# NinjaPCB_ver2_0.net
KiCad netlist of a schematic drawn in EAGLE
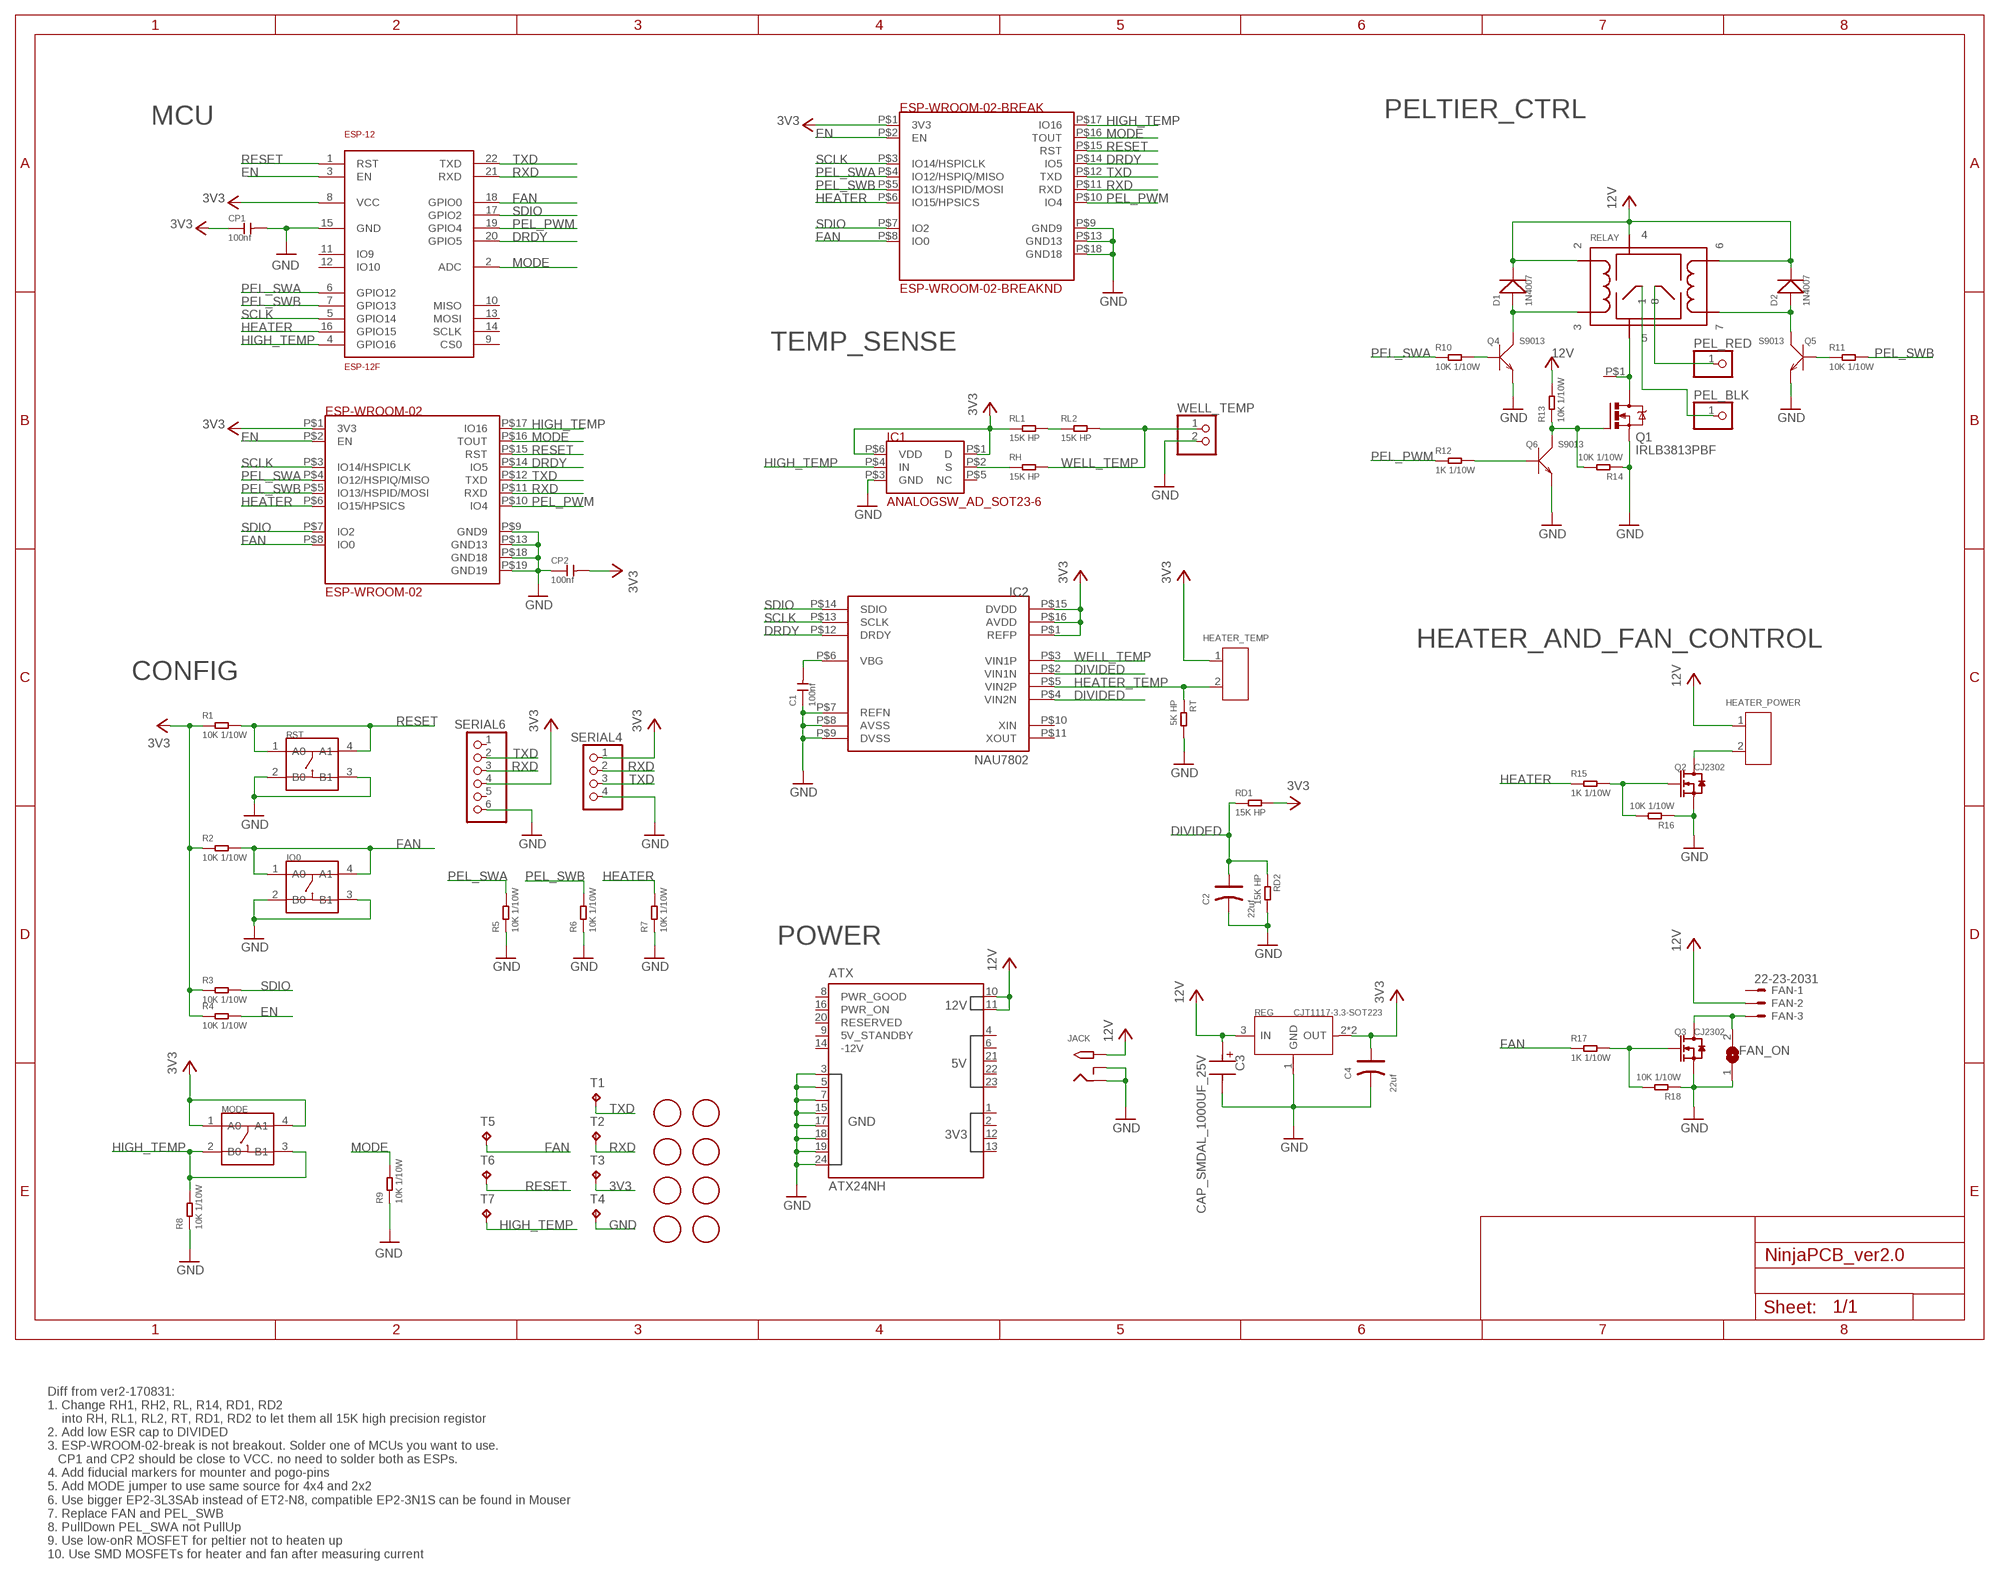
[diagram p0: schematic, sheet 1]

(export (version "E")
  (design (tool "Eeschema 10.0.6"))
  (components
    (comp (ref "ATX")
      (value "ATX24NH")
      (footprint "eagle-import:ATX24")
      (libsource (lib "eagle-import") (part "ATX24NH"))
    )
    (comp (ref "C1")
      (value "100nf")
      (footprint "eagle-import:C0603")
      (fields (field (name "MPN") "CC0603KRX7R9BB104"))
      (libsource (lib "eagle-import") (part "CERAMIC-100NF-50V-10%-X7R(0603)"))
    )
    (comp (ref "C2")
      (value "22uf")
      (footprint "eagle-import:AVX-B")
      (fields (field (name "MPN") "TAJB226*016#NJ"))
      (libsource (lib "eagle-import") (part "TANTALUM-SMD-22UF-16V(AVX-B)"))
    )
    (comp (ref "C3")
      (value "CAP_SMDAL_1000UF_25V")
      (footprint "eagle-import:CAP_SMD_AL_D125")
      (libsource (lib "eagle-import") (part "CAP_SMDAL_1000UF_25V"))
    )
    (comp (ref "C4")
      (value "22uf")
      (footprint "eagle-import:AVX-B")
      (fields (field (name "MPN") "TAJB226*016#NJ"))
      (libsource (lib "eagle-import") (part "TANTALUM-SMD-22UF-16V(AVX-B)"))
    )
    (comp (ref "CP1")
      (value "100nf")
      (footprint "eagle-import:C0603")
      (fields (field (name "MPN") "CC0603KRX7R9BB104"))
      (libsource (lib "eagle-import") (part "CERAMIC-100NF-50V-10%-X7R(0603)"))
    )
    (comp (ref "CP2")
      (value "100nf")
      (footprint "eagle-import:C0603")
      (fields (field (name "MPN") "CC0603KRX7R9BB104"))
      (libsource (lib "eagle-import") (part "CERAMIC-100NF-50V-10%-X7R(0603)"))
    )
    (comp (ref "D1")
      (value "1N4007")
      (footprint "eagle-import:DO-214AC")
      (libsource (lib "eagle-import") (part "DIODE-GEN-PURPOSE-1KV-1A(DO-214AC)"))
    )
    (comp (ref "D2")
      (value "1N4007")
      (footprint "eagle-import:DO-214AC")
      (libsource (lib "eagle-import") (part "DIODE-GEN-PURPOSE-1KV-1A(DO-214AC)"))
    )
    (comp (ref "ESP-12")
      (value "ESP-12F")
      (footprint "eagle-import:ESP-12F")
      (libsource (lib "eagle-import") (part "ESP-12F"))
    )
    (comp (ref "ESP-WROOM-02")
      (value "ESP-WROOM-02")
      (footprint "eagle-import:ESP-WROOM-02")
      (libsource (lib "eagle-import") (part "ESP-WROOM-02"))
    )
    (comp (ref "ESP-WROOM-02-BREAK")
      (value "ESP-WROOM-02-BREAKND")
      (footprint "eagle-import:ESP-WROOM-02-BREAK-NODETAIL")
      (libsource (lib "eagle-import") (part "ESP-WROOM-02-BREAKND"))
    )
    (comp (ref "FAN")
      (value "22-23-2031")
      (footprint "eagle-import:22-23-2031")
      (fields (field (name "MF") "MOLEX"))
      (libsource (lib "eagle-import") (part "22-23-2031"))
    )
    (comp (ref "FAN_ON")
      (value "SJ")
      (footprint "eagle-import:SJ")
      (libsource (lib "eagle-import") (part "SJ"))
    )
    (comp (ref "HEATER_POWER")
      (value "SCREW-TERMINAL-GREEN(2P-3.5)")
      (footprint "eagle-import:H2-3.5-7.0X7.0MM")
      (libsource (lib "eagle-import") (part "SCREW-TERMINAL-GREEN(2P-3.5)"))
    )
    (comp (ref "HEATER_TEMP")
      (value "SCREW-TERMINAL-GREEN(2P-3.5)")
      (footprint "eagle-import:H2-3.5-7.0X7.0MM")
      (libsource (lib "eagle-import") (part "SCREW-TERMINAL-GREEN(2P-3.5)"))
    )
    (comp (ref "HEATSINK")
      (value "HEAT111PB015")
      (footprint "eagle-import:HEAT11PB015")
      (libsource (lib "eagle-import") (part "HEAT111PB015"))
    )
    (comp (ref "IC1")
      (value "ANALOGSW_AD_SOT23-6")
      (footprint "eagle-import:SOT-23-6")
      (libsource (lib "eagle-import") (part "ANALOGSW_AD_SOT23-6"))
    )
    (comp (ref "IC2")
      (value "NAU7802")
      (footprint "eagle-import:SOP-16")
      (libsource (lib "eagle-import") (part "NAU7802"))
    )
    (comp (ref "IO0")
      (value "DIP-SWITCH-TACTILE-SPST-NO/TS-1109(4P-D6.0MM)'TS-1109'")
      (footprint "eagle-import:SW4-6.0X6.0X5.0MM")
      (libsource (lib "eagle-import") (part "DIP-SWITCH-TACTILE-SPST-NO/TS-1109(4P-D6.0MM)'TS-1109'"))
    )
    (comp (ref "JACK")
      (value "2.1MMJACKTHM-NOOUT")
      (footprint "eagle-import:PJ-102A-NOOUT")
      (libsource (lib "eagle-import") (part "2.1MMJACKTHM-NOOUT"))
    )
    (comp (ref "MODE")
      (value "DIP-SWITCH-TACTILE-SPST-NO/TS-1109(4P-D6.0MM)'TS-1109'")
      (footprint "eagle-import:SW4-6.0X6.0X5.0MM")
      (libsource (lib "eagle-import") (part "DIP-SWITCH-TACTILE-SPST-NO/TS-1109(4P-D6.0MM)'TS-1109'"))
    )
    (comp (ref "PEL_BLK")
      (value "PINHD-1X1L")
      (footprint "eagle-import:1X01LONG")
      (libsource (lib "eagle-import") (part "PINHD-1X1L"))
    )
    (comp (ref "PEL_RED")
      (value "PINHD-1X1L")
      (footprint "eagle-import:1X01LONG")
      (libsource (lib "eagle-import") (part "PINHD-1X1L"))
    )
    (comp (ref "Q1")
      (value "IRLB3813PBF")
      (footprint "eagle-import:TO220BV")
      (libsource (lib "eagle-import") (part "IRF520"))
    )
    (comp (ref "Q2")
      (value "CJ2302")
      (footprint "eagle-import:SOT-23")
      (libsource (lib "eagle-import") (part "SMD-MOSFET-N-CH-20V-2.1A-CJ2302(SOT-23)"))
    )
    (comp (ref "Q3")
      (value "CJ2302")
      (footprint "eagle-import:SOT-23")
      (libsource (lib "eagle-import") (part "SMD-MOSFET-N-CH-20V-2.1A-CJ2302(SOT-23)"))
    )
    (comp (ref "Q4")
      (value "S9013")
      (footprint "eagle-import:SOT-23")
      (libsource (lib "eagle-import") (part "SMD-TRANSISTORS-NPN-25V-500MA-S9013(SOT-23)"))
    )
    (comp (ref "Q5")
      (value "S9013")
      (footprint "eagle-import:SOT-23")
      (libsource (lib "eagle-import") (part "SMD-TRANSISTORS-NPN-25V-500MA-S9013(SOT-23)"))
    )
    (comp (ref "Q6")
      (value "S9013")
      (footprint "eagle-import:SOT-23")
      (libsource (lib "eagle-import") (part "SMD-TRANSISTORS-NPN-25V-500MA-S9013(SOT-23)"))
    )
    (comp (ref "R1")
      (value "10K 1/10W")
      (footprint "eagle-import:R0603")
      (fields (field (name "MPN") "RC0603JR-0710KL"))
      (libsource (lib "eagle-import") (part "SMD-RES-10K-5%-1/10W(0603)"))
    )
    (comp (ref "R2")
      (value "10K 1/10W")
      (footprint "eagle-import:R0603")
      (fields (field (name "MPN") "RC0603JR-0710KL"))
      (libsource (lib "eagle-import") (part "SMD-RES-10K-5%-1/10W(0603)"))
    )
    (comp (ref "R3")
      (value "10K 1/10W")
      (footprint "eagle-import:R0603")
      (fields (field (name "MPN") "RC0603JR-0710KL"))
      (libsource (lib "eagle-import") (part "SMD-RES-10K-5%-1/10W(0603)"))
    )
    (comp (ref "R4")
      (value "10K 1/10W")
      (footprint "eagle-import:R0603")
      (fields (field (name "MPN") "RC0603JR-0710KL"))
      (libsource (lib "eagle-import") (part "SMD-RES-10K-5%-1/10W(0603)"))
    )
    (comp (ref "R5")
      (value "10K 1/10W")
      (footprint "eagle-import:R0603")
      (fields (field (name "MPN") "RC0603JR-0710KL"))
      (libsource (lib "eagle-import") (part "SMD-RES-10K-5%-1/10W(0603)"))
    )
    (comp (ref "R6")
      (value "10K 1/10W")
      (footprint "eagle-import:R0603")
      (fields (field (name "MPN") "RC0603JR-0710KL"))
      (libsource (lib "eagle-import") (part "SMD-RES-10K-5%-1/10W(0603)"))
    )
    (comp (ref "R7")
      (value "10K 1/10W")
      (footprint "eagle-import:R0603")
      (fields (field (name "MPN") "RC0603JR-0710KL"))
      (libsource (lib "eagle-import") (part "SMD-RES-10K-5%-1/10W(0603)"))
    )
    (comp (ref "R8")
      (value "10K 1/10W")
      (footprint "eagle-import:R0603")
      (fields (field (name "MPN") "RC0603JR-0710KL"))
      (libsource (lib "eagle-import") (part "SMD-RES-10K-5%-1/10W(0603)"))
    )
    (comp (ref "R9")
      (value "10K 1/10W")
      (footprint "eagle-import:R0603")
      (fields (field (name "MPN") "RC0603JR-0710KL"))
      (libsource (lib "eagle-import") (part "SMD-RES-10K-5%-1/10W(0603)"))
    )
    (comp (ref "R10")
      (value "10K 1/10W")
      (footprint "eagle-import:R0603")
      (fields (field (name "MPN") "RC0603JR-0710KL"))
      (libsource (lib "eagle-import") (part "SMD-RES-10K-5%-1/10W(0603)"))
    )
    (comp (ref "R11")
      (value "10K 1/10W")
      (footprint "eagle-import:R0603")
      (fields (field (name "MPN") "RC0603JR-0710KL"))
      (libsource (lib "eagle-import") (part "SMD-RES-10K-5%-1/10W(0603)"))
    )
    (comp (ref "R12")
      (value "1K 1/10W")
      (footprint "eagle-import:R0603")
      (fields (field (name "MPN") "RC0603JR-071KL"))
      (libsource (lib "eagle-import") (part "SMD-RES-1K-5%-1/10W(0603)"))
    )
    (comp (ref "R13")
      (value "10K 1/10W")
      (footprint "eagle-import:R0603")
      (fields (field (name "MPN") "RC0603JR-0710KL"))
      (libsource (lib "eagle-import") (part "SMD-RES-10K-5%-1/10W(0603)"))
    )
    (comp (ref "R14")
      (value "10K 1/10W")
      (footprint "eagle-import:R0603")
      (fields (field (name "MPN") "RC0603JR-0710KL"))
      (libsource (lib "eagle-import") (part "SMD-RES-10K-5%-1/10W(0603)"))
    )
    (comp (ref "R15")
      (value "1K 1/10W")
      (footprint "eagle-import:R0603")
      (fields (field (name "MPN") "RC0603JR-071KL"))
      (libsource (lib "eagle-import") (part "SMD-RES-1K-5%-1/10W(0603)"))
    )
    (comp (ref "R16")
      (value "10K 1/10W")
      (footprint "eagle-import:R0603")
      (fields (field (name "MPN") "RC0603JR-0710KL"))
      (libsource (lib "eagle-import") (part "SMD-RES-10K-5%-1/10W(0603)"))
    )
    (comp (ref "R17")
      (value "1K 1/10W")
      (footprint "eagle-import:R0603")
      (fields (field (name "MPN") "RC0603JR-071KL"))
      (libsource (lib "eagle-import") (part "SMD-RES-1K-5%-1/10W(0603)"))
    )
    (comp (ref "R18")
      (value "10K 1/10W")
      (footprint "eagle-import:R0603")
      (fields (field (name "MPN") "RC0603JR-0710KL"))
      (libsource (lib "eagle-import") (part "SMD-RES-10K-5%-1/10W(0603)"))
    )
    (comp (ref "RD1")
      (value "15K HP")
      (footprint "eagle-import:R0603")
      (libsource (lib "eagle-import") (part "R0603"))
    )
    (comp (ref "RD2")
      (value "15K HP")
      (footprint "eagle-import:R0603")
      (libsource (lib "eagle-import") (part "R0603"))
    )
    (comp (ref "REG")
      (value "CJT1117-3.3-SOT223")
      (footprint "eagle-import:SOT-223")
      (fields (field (name "MPN") "CJT1117-3.3"))
      (libsource (lib "eagle-import") (part "PMIC-CJT1117-3.3(SOT223)"))
    )
    (comp (ref "RELAY")
      (value "NEC-RELAY2EN2")
      (footprint "eagle-import:NEC-EN2")
      (libsource (lib "eagle-import") (part "NEC-RELAY2EN2"))
    )
    (comp (ref "RH")
      (value "15K HP")
      (footprint "eagle-import:R0603")
      (libsource (lib "eagle-import") (part "R0603"))
    )
    (comp (ref "RL1")
      (value "15K HP")
      (footprint "eagle-import:R0603")
      (libsource (lib "eagle-import") (part "R0603"))
    )
    (comp (ref "RL2")
      (value "15K HP")
      (footprint "eagle-import:R0603")
      (libsource (lib "eagle-import") (part "R0603"))
    )
    (comp (ref "RST")
      (value "DIP-SWITCH-TACTILE-SPST-NO/TS-1109(4P-D6.0MM)'TS-1109'")
      (footprint "eagle-import:SW4-6.0X6.0X5.0MM")
      (libsource (lib "eagle-import") (part "DIP-SWITCH-TACTILE-SPST-NO/TS-1109(4P-D6.0MM)'TS-1109'"))
    )
    (comp (ref "RT")
      (value "5K HP")
      (footprint "eagle-import:R0603")
      (fields (field (name "MPN") "RC0603FR-072KL"))
      (libsource (lib "eagle-import") (part "SMD-RES-2K-1%-1/10W(0603)"))
    )
    (comp (ref "SERIAL4")
      (value "PINHD-1X4")
      (footprint "eagle-import:1X04")
      (libsource (lib "eagle-import") (part "PINHD-1X4"))
    )
    (comp (ref "SERIAL6")
      (value "PINHD-1X6")
      (footprint "eagle-import:1X06")
      (libsource (lib "eagle-import") (part "PINHD-1X6"))
    )
    (comp (ref "T1")
      (value "TPTP20R")
      (footprint "eagle-import:TP20R")
      (libsource (lib "eagle-import") (part "TPTP20R"))
    )
    (comp (ref "T2")
      (value "TPTP20R")
      (footprint "eagle-import:TP20R")
      (libsource (lib "eagle-import") (part "TPTP20R"))
    )
    (comp (ref "T3")
      (value "TPTP20R")
      (footprint "eagle-import:TP20R")
      (libsource (lib "eagle-import") (part "TPTP20R"))
    )
    (comp (ref "T4")
      (value "TPTP20R")
      (footprint "eagle-import:TP20R")
      (libsource (lib "eagle-import") (part "TPTP20R"))
    )
    (comp (ref "T5")
      (value "TPTP20R")
      (footprint "eagle-import:TP20R")
      (libsource (lib "eagle-import") (part "TPTP20R"))
    )
    (comp (ref "T6")
      (value "TPTP20R")
      (footprint "eagle-import:TP20R")
      (libsource (lib "eagle-import") (part "TPTP20R"))
    )
    (comp (ref "T7")
      (value "TPTP20R")
      (footprint "eagle-import:TP20R")
      (libsource (lib "eagle-import") (part "TPTP20R"))
    )
    (comp (ref "U$3")
      (value "FIDUCIAL")
      (footprint "eagle-import:FIDUCIAL_1MM")
      (libsource (lib "eagle-import") (part "FIDUCIAL"))
    )
    (comp (ref "U$4")
      (value "FIDUCIAL")
      (footprint "eagle-import:FIDUCIAL_1MM")
      (libsource (lib "eagle-import") (part "FIDUCIAL"))
    )
    (comp (ref "U$5")
      (value "FIDUCIAL")
      (footprint "eagle-import:FIDUCIAL_1MM")
      (libsource (lib "eagle-import") (part "FIDUCIAL"))
    )
    (comp (ref "U$6")
      (value "FIDUCIAL")
      (footprint "eagle-import:FIDUCIAL_1MM")
      (libsource (lib "eagle-import") (part "FIDUCIAL"))
    )
    (comp (ref "U$7")
      (value "FIDUCIAL")
      (footprint "eagle-import:FIDUCIAL_1MM")
      (libsource (lib "eagle-import") (part "FIDUCIAL"))
    )
    (comp (ref "U$8")
      (value "FIDUCIAL")
      (footprint "eagle-import:FIDUCIAL_1MM")
      (libsource (lib "eagle-import") (part "FIDUCIAL"))
    )
    (comp (ref "U$9")
      (value "FIDUCIAL")
      (footprint "eagle-import:FIDUCIAL_1MM")
      (libsource (lib "eagle-import") (part "FIDUCIAL"))
    )
    (comp (ref "U$10")
      (value "FIDUCIAL")
      (footprint "eagle-import:FIDUCIAL_1MM")
      (libsource (lib "eagle-import") (part "FIDUCIAL"))
    )
    (comp (ref "WELL_TEMP")
      (value "PINHD-1X2")
      (footprint "eagle-import:1X02")
      (libsource (lib "eagle-import") (part "PINHD-1X2"))
    )
  )
  (nets
    (net (code "1") (name "/DIVIDED") (class "Default")
      (node (ref "C2") (pin "+") (pinfunction "+_+") (pintype "passive"))
      (node (ref "IC2") (pin "P$2") (pinfunction "VIN1N_P$2") (pintype "bidirectional"))
      (node (ref "IC2") (pin "P$4") (pinfunction "VIN2N_P$4") (pintype "bidirectional"))
      (node (ref "RD1") (pin "1") (pinfunction "1_1") (pintype "passive"))
      (node (ref "RD2") (pin "1") (pinfunction "1_1") (pintype "passive"))
    )
    (net (code "2") (name "/DRDY") (class "Default")
      (node (ref "ESP-12") (pin "20") (pinfunction "GPIO5_20") (pintype "bidirectional"))
      (node (ref "ESP-WROOM-02") (pin "P$14") (pinfunction "IO5_P$14") (pintype "bidirectional"))
      (node (ref "ESP-WROOM-02-BREAK") (pin "P$14") (pinfunction "IO5_P$14") (pintype "bidirectional"))
      (node (ref "IC2") (pin "P$12") (pinfunction "DRDY_P$12") (pintype "bidirectional"))
    )
    (net (code "3") (name "/EN") (class "Default")
      (node (ref "ESP-12") (pin "3") (pinfunction "EN_3") (pintype "bidirectional"))
      (node (ref "ESP-WROOM-02") (pin "P$2") (pinfunction "EN_P$2") (pintype "bidirectional"))
      (node (ref "ESP-WROOM-02-BREAK") (pin "P$2") (pinfunction "EN_P$2") (pintype "bidirectional"))
      (node (ref "R4") (pin "2") (pinfunction "2_2") (pintype "passive"))
    )
    (net (code "4") (name "/FAN") (class "Default")
      (node (ref "ESP-12") (pin "18") (pinfunction "GPIO0_18") (pintype "bidirectional"))
      (node (ref "ESP-WROOM-02") (pin "P$8") (pinfunction "IO0_P$8") (pintype "bidirectional"))
      (node (ref "ESP-WROOM-02-BREAK") (pin "P$8") (pinfunction "IO0_P$8") (pintype "bidirectional"))
      (node (ref "IO0") (pin "1") (pinfunction "A0_1") (pintype "bidirectional"))
      (node (ref "IO0") (pin "4") (pinfunction "A1_4") (pintype "bidirectional"))
      (node (ref "R17") (pin "1") (pinfunction "1_1") (pintype "passive"))
      (node (ref "R2") (pin "2") (pinfunction "2_2") (pintype "passive"))
      (node (ref "T5") (pin "TP") (pinfunction "TP_TP") (pintype "input"))
    )
    (net (code "5") (name "/HEATER") (class "Default")
      (node (ref "ESP-12") (pin "16") (pinfunction "GPIO15_16") (pintype "bidirectional"))
      (node (ref "ESP-WROOM-02") (pin "P$6") (pinfunction "IO15/HPSICS_P$6") (pintype "bidirectional"))
      (node (ref "ESP-WROOM-02-BREAK") (pin "P$6") (pinfunction "IO15/HPSICS_P$6") (pintype "bidirectional"))
      (node (ref "R15") (pin "1") (pinfunction "1_1") (pintype "passive"))
      (node (ref "R7") (pin "2") (pinfunction "2_2") (pintype "passive"))
    )
    (net (code "6") (name "/HEATER_TEMP") (class "Default")
      (node (ref "HEATER_TEMP") (pin "2") (pinfunction "2_2") (pintype "bidirectional"))
      (node (ref "IC2") (pin "P$5") (pinfunction "VIN2P_P$5") (pintype "bidirectional"))
      (node (ref "RT") (pin "1") (pinfunction "1_1") (pintype "passive"))
    )
    (net (code "7") (name "/HIGH_TEMP") (class "Default")
      (node (ref "ESP-12") (pin "4") (pinfunction "GPIO16_4") (pintype "bidirectional"))
      (node (ref "ESP-WROOM-02") (pin "P$17") (pinfunction "IO16_P$17") (pintype "bidirectional"))
      (node (ref "ESP-WROOM-02-BREAK") (pin "P$17") (pinfunction "IO16_P$17") (pintype "bidirectional"))
      (node (ref "IC1") (pin "P$4") (pinfunction "IN_P$4") (pintype "bidirectional"))
      (node (ref "MODE") (pin "2") (pinfunction "B0_2") (pintype "bidirectional"))
      (node (ref "MODE") (pin "3") (pinfunction "B1_3") (pintype "bidirectional"))
      (node (ref "R8") (pin "2") (pinfunction "2_2") (pintype "passive"))
      (node (ref "T7") (pin "TP") (pinfunction "TP_TP") (pintype "input"))
    )
    (net (code "8") (name "/MODE") (class "Default")
      (node (ref "ESP-12") (pin "2") (pinfunction "ADC_2") (pintype "bidirectional"))
      (node (ref "ESP-WROOM-02") (pin "P$16") (pinfunction "TOUT_P$16") (pintype "bidirectional"))
      (node (ref "ESP-WROOM-02-BREAK") (pin "P$16") (pinfunction "TOUT_P$16") (pintype "bidirectional"))
      (node (ref "R9") (pin "2") (pinfunction "2_2") (pintype "passive"))
    )
    (net (code "9") (name "/PEL_PWM") (class "Default")
      (node (ref "ESP-12") (pin "19") (pinfunction "GPIO4_19") (pintype "bidirectional"))
      (node (ref "ESP-WROOM-02") (pin "P$10") (pinfunction "IO4_P$10") (pintype "bidirectional"))
      (node (ref "ESP-WROOM-02-BREAK") (pin "P$10") (pinfunction "IO4_P$10") (pintype "bidirectional"))
      (node (ref "R12") (pin "1") (pinfunction "1_1") (pintype "passive"))
    )
    (net (code "10") (name "/PEL_SWA") (class "Default")
      (node (ref "ESP-12") (pin "6") (pinfunction "GPIO12_6") (pintype "bidirectional"))
      (node (ref "ESP-WROOM-02") (pin "P$4") (pinfunction "IO12/HSPIQ/MISO_P$4") (pintype "bidirectional"))
      (node (ref "ESP-WROOM-02-BREAK") (pin "P$4") (pinfunction "IO12/HSPIQ/MISO_P$4") (pintype "bidirectional"))
      (node (ref "R10") (pin "1") (pinfunction "1_1") (pintype "passive"))
      (node (ref "R5") (pin "2") (pinfunction "2_2") (pintype "passive"))
    )
    (net (code "11") (name "/PEL_SWB") (class "Default")
      (node (ref "ESP-12") (pin "7") (pinfunction "GPIO13_7") (pintype "bidirectional"))
      (node (ref "ESP-WROOM-02") (pin "P$5") (pinfunction "IO13/HSPID/MOSI_P$5") (pintype "bidirectional"))
      (node (ref "ESP-WROOM-02-BREAK") (pin "P$5") (pinfunction "IO13/HSPID/MOSI_P$5") (pintype "bidirectional"))
      (node (ref "R11") (pin "2") (pinfunction "2_2") (pintype "passive"))
      (node (ref "R6") (pin "2") (pinfunction "2_2") (pintype "passive"))
    )
    (net (code "12") (name "/RESET") (class "Default")
      (node (ref "ESP-12") (pin "1") (pinfunction "RST_1") (pintype "bidirectional"))
      (node (ref "ESP-WROOM-02") (pin "P$15") (pinfunction "RST_P$15") (pintype "bidirectional"))
      (node (ref "ESP-WROOM-02-BREAK") (pin "P$15") (pinfunction "RST_P$15") (pintype "bidirectional"))
      (node (ref "R1") (pin "2") (pinfunction "2_2") (pintype "passive"))
      (node (ref "RST") (pin "1") (pinfunction "A0_1") (pintype "bidirectional"))
      (node (ref "RST") (pin "4") (pinfunction "A1_4") (pintype "bidirectional"))
      (node (ref "T6") (pin "TP") (pinfunction "TP_TP") (pintype "input"))
    )
    (net (code "13") (name "/RXD") (class "Default")
      (node (ref "ESP-12") (pin "21") (pinfunction "RXD_21") (pintype "bidirectional"))
      (node (ref "ESP-WROOM-02") (pin "P$11") (pinfunction "RXD_P$11") (pintype "bidirectional"))
      (node (ref "ESP-WROOM-02-BREAK") (pin "P$11") (pinfunction "RXD_P$11") (pintype "bidirectional"))
      (node (ref "SERIAL4") (pin "2") (pinfunction "2_2") (pintype "passive"))
      (node (ref "SERIAL6") (pin "3") (pinfunction "3_3") (pintype "passive"))
      (node (ref "T2") (pin "TP") (pinfunction "TP_TP") (pintype "input"))
    )
    (net (code "14") (name "/SCLK") (class "Default")
      (node (ref "ESP-12") (pin "5") (pinfunction "GPIO14_5") (pintype "bidirectional"))
      (node (ref "ESP-WROOM-02") (pin "P$3") (pinfunction "IO14/HSPICLK_P$3") (pintype "bidirectional"))
      (node (ref "ESP-WROOM-02-BREAK") (pin "P$3") (pinfunction "IO14/HSPICLK_P$3") (pintype "bidirectional"))
      (node (ref "IC2") (pin "P$13") (pinfunction "SCLK_P$13") (pintype "bidirectional"))
    )
    (net (code "15") (name "/SDIO") (class "Default")
      (node (ref "ESP-12") (pin "17") (pinfunction "GPIO2_17") (pintype "bidirectional"))
      (node (ref "ESP-WROOM-02") (pin "P$7") (pinfunction "IO2_P$7") (pintype "bidirectional"))
      (node (ref "ESP-WROOM-02-BREAK") (pin "P$7") (pinfunction "IO2_P$7") (pintype "bidirectional"))
      (node (ref "IC2") (pin "P$14") (pinfunction "SDIO_P$14") (pintype "bidirectional"))
      (node (ref "R3") (pin "2") (pinfunction "2_2") (pintype "passive"))
    )
    (net (code "16") (name "/TXD") (class "Default")
      (node (ref "ESP-12") (pin "22") (pinfunction "TXD_22") (pintype "bidirectional"))
      (node (ref "ESP-WROOM-02") (pin "P$12") (pinfunction "TXD_P$12") (pintype "bidirectional"))
      (node (ref "ESP-WROOM-02-BREAK") (pin "P$12") (pinfunction "TXD_P$12") (pintype "bidirectional"))
      (node (ref "SERIAL4") (pin "3") (pinfunction "3_3") (pintype "passive"))
      (node (ref "SERIAL6") (pin "2") (pinfunction "2_2") (pintype "passive"))
      (node (ref "T1") (pin "TP") (pinfunction "TP_TP") (pintype "input"))
    )
    (net (code "17") (name "/WELL_TEMP") (class "Default")
      (node (ref "IC2") (pin "P$3") (pinfunction "VIN1P_P$3") (pintype "bidirectional"))
      (node (ref "RH") (pin "2") (pinfunction "2_2") (pintype "passive"))
      (node (ref "RL2") (pin "2") (pinfunction "2_2") (pintype "passive"))
      (node (ref "WELL_TEMP") (pin "1") (pinfunction "1_1") (pintype "passive"))
    )
    (net (code "18") (name "3V3") (class "Default")
      (node (ref "C4") (pin "+") (pinfunction "+_+") (pintype "passive"))
      (node (ref "CP1") (pin "1") (pinfunction "1_1") (pintype "passive"))
      (node (ref "CP2") (pin "2") (pinfunction "2_2") (pintype "passive"))
      (node (ref "ESP-12") (pin "8") (pinfunction "VCC_8") (pintype "bidirectional"))
      (node (ref "ESP-WROOM-02") (pin "P$1") (pinfunction "3V3_P$1") (pintype "bidirectional"))
      (node (ref "ESP-WROOM-02-BREAK") (pin "P$1") (pinfunction "3V3_P$1") (pintype "bidirectional"))
      (node (ref "HEATER_TEMP") (pin "1") (pinfunction "1_1") (pintype "bidirectional"))
      (node (ref "IC1") (pin "P$1") (pinfunction "D_P$1") (pintype "bidirectional"))
      (node (ref "IC1") (pin "P$6") (pinfunction "VDD_P$6") (pintype "bidirectional"))
      (node (ref "IC2") (pin "P$1") (pinfunction "REFP_P$1") (pintype "bidirectional"))
      (node (ref "IC2") (pin "P$15") (pinfunction "DVDD_P$15") (pintype "bidirectional"))
      (node (ref "IC2") (pin "P$16") (pinfunction "AVDD_P$16") (pintype "bidirectional"))
      (node (ref "MODE") (pin "1") (pinfunction "A0_1") (pintype "bidirectional"))
      (node (ref "MODE") (pin "4") (pinfunction "A1_4") (pintype "bidirectional"))
      (node (ref "R1") (pin "1") (pinfunction "1_1") (pintype "passive"))
      (node (ref "R2") (pin "1") (pinfunction "1_1") (pintype "passive"))
      (node (ref "R3") (pin "1") (pinfunction "1_1") (pintype "passive"))
      (node (ref "R4") (pin "1") (pinfunction "1_1") (pintype "passive"))
      (node (ref "RD1") (pin "2") (pinfunction "2_2") (pintype "passive"))
      (node (ref "REG") (pin "2") (pinfunction "OUT_2") (pintype "bidirectional"))
      (node (ref "REG") (pin "TER") (pinfunction "OUT_TER") (pintype "bidirectional"))
      (node (ref "RL1") (pin "1") (pinfunction "1_1") (pintype "passive"))
      (node (ref "SERIAL4") (pin "1") (pinfunction "1_1") (pintype "passive"))
      (node (ref "SERIAL6") (pin "4") (pinfunction "4_4") (pintype "passive"))
      (node (ref "T3") (pin "TP") (pinfunction "TP_TP") (pintype "input"))
    )
    (net (code "19") (name "12V") (class "Default")
      (node (ref "ATX") (pin "10") (pinfunction "12V_10_10") (pintype "bidirectional"))
      (node (ref "ATX") (pin "11") (pinfunction "12V_11_11") (pintype "bidirectional"))
      (node (ref "C3") (pin "P$P") (pinfunction "P$P_P$P") (pintype "passive"))
      (node (ref "D1") (pin "2") (pinfunction "-_2") (pintype "passive"))
      (node (ref "D2") (pin "2") (pinfunction "-_2") (pintype "passive"))
      (node (ref "FAN") (pin "2") (pinfunction "S_2") (pintype "passive"))
      (node (ref "HEATER_POWER") (pin "1") (pinfunction "1_1") (pintype "bidirectional"))
      (node (ref "JACK") (pin "TIP") (pinfunction "TIP_TIP") (pintype "bidirectional"))
      (node (ref "R13") (pin "2") (pinfunction "2_2") (pintype "passive"))
      (node (ref "REG") (pin "3") (pinfunction "IN_3") (pintype "bidirectional"))
      (node (ref "RELAY") (pin "P$2") (pinfunction "2_P$2") (pintype "bidirectional"))
      (node (ref "RELAY") (pin "P$4") (pinfunction "4_P$4") (pintype "bidirectional"))
      (node (ref "RELAY") (pin "P$6") (pinfunction "6_P$6") (pintype "bidirectional"))
    )
    (net (code "20") (name "GND") (class "Default")
      (node (ref "ATX") (pin "15") (pinfunction "GND15_15") (pintype "bidirectional"))
      (node (ref "ATX") (pin "17") (pinfunction "GND17_17") (pintype "bidirectional"))
      (node (ref "ATX") (pin "18") (pinfunction "GND18_18") (pintype "bidirectional"))
      (node (ref "ATX") (pin "19") (pinfunction "GND19_19") (pintype "bidirectional"))
      (node (ref "ATX") (pin "24") (pinfunction "GND24_24") (pintype "bidirectional"))
      (node (ref "ATX") (pin "3") (pinfunction "GND3_3") (pintype "bidirectional"))
      (node (ref "ATX") (pin "5") (pinfunction "GND5_5") (pintype "bidirectional"))
      (node (ref "ATX") (pin "7") (pinfunction "GND7_7") (pintype "bidirectional"))
      (node (ref "C1") (pin "1") (pinfunction "1_1") (pintype "passive"))
      (node (ref "C2") (pin "-") (pinfunction "-_-") (pintype "passive"))
      (node (ref "C3") (pin "P$M") (pinfunction "P$M_P$M") (pintype "passive"))
      (node (ref "C4") (pin "-") (pinfunction "-_-") (pintype "passive"))
      (node (ref "CP1") (pin "2") (pinfunction "2_2") (pintype "passive"))
      (node (ref "CP2") (pin "1") (pinfunction "1_1") (pintype "passive"))
      (node (ref "ESP-12") (pin "15") (pinfunction "GND_15") (pintype "bidirectional"))
      (node (ref "ESP-WROOM-02") (pin "P$13") (pinfunction "GND13_P$13") (pintype "bidirectional"))
      (node (ref "ESP-WROOM-02") (pin "P$18") (pinfunction "GND18_P$18") (pintype "bidirectional"))
      (node (ref "ESP-WROOM-02") (pin "P$19") (pinfunction "GND19_P$19") (pintype "bidirectional"))
      (node (ref "ESP-WROOM-02") (pin "P$9") (pinfunction "GND9_P$9") (pintype "bidirectional"))
      (node (ref "ESP-WROOM-02-BREAK") (pin "P$13") (pinfunction "GND13_P$13") (pintype "bidirectional"))
      (node (ref "ESP-WROOM-02-BREAK") (pin "P$18") (pinfunction "GND18_P$18") (pintype "bidirectional"))
      (node (ref "ESP-WROOM-02-BREAK") (pin "P$9") (pinfunction "GND9_P$9") (pintype "bidirectional"))
      (node (ref "FAN_ON") (pin "1") (pinfunction "1_1") (pintype "passive"))
      (node (ref "IC1") (pin "P$3") (pinfunction "GND_P$3") (pintype "bidirectional"))
      (node (ref "IC2") (pin "P$7") (pinfunction "REFN_P$7") (pintype "bidirectional"))
      (node (ref "IC2") (pin "P$8") (pinfunction "AVSS_P$8") (pintype "bidirectional"))
      (node (ref "IC2") (pin "P$9") (pinfunction "DVSS_P$9") (pintype "bidirectional"))
      (node (ref "IO0") (pin "2") (pinfunction "B0_2") (pintype "bidirectional"))
      (node (ref "IO0") (pin "3") (pinfunction "B1_3") (pintype "bidirectional"))
      (node (ref "JACK") (pin "RING") (pinfunction "RING_RING") (pintype "bidirectional"))
      (node (ref "JACK") (pin "RING_SW") (pinfunction "RING_SW_RING_SW") (pintype "bidirectional"))
      (node (ref "Q1") (pin "S") (pinfunction "S_S") (pintype "passive"))
      (node (ref "Q2") (pin "2") (pinfunction "S_2") (pintype "passive"))
      (node (ref "Q3") (pin "2") (pinfunction "S_2") (pintype "passive"))
      (node (ref "Q4") (pin "2") (pinfunction "E_2") (pintype "passive"))
      (node (ref "Q5") (pin "2") (pinfunction "E_2") (pintype "passive"))
      (node (ref "Q6") (pin "2") (pinfunction "E_2") (pintype "passive"))
      (node (ref "R14") (pin "1") (pinfunction "1_1") (pintype "passive"))
      (node (ref "R16") (pin "1") (pinfunction "1_1") (pintype "passive"))
      (node (ref "R18") (pin "1") (pinfunction "1_1") (pintype "passive"))
      (node (ref "R5") (pin "1") (pinfunction "1_1") (pintype "passive"))
      (node (ref "R6") (pin "1") (pinfunction "1_1") (pintype "passive"))
      (node (ref "R7") (pin "1") (pinfunction "1_1") (pintype "passive"))
      (node (ref "R8") (pin "1") (pinfunction "1_1") (pintype "passive"))
      (node (ref "R9") (pin "1") (pinfunction "1_1") (pintype "passive"))
      (node (ref "RD2") (pin "2") (pinfunction "2_2") (pintype "passive"))
      (node (ref "REG") (pin "1") (pinfunction "GND_1") (pintype "bidirectional"))
      (node (ref "RST") (pin "2") (pinfunction "B0_2") (pintype "bidirectional"))
      (node (ref "RST") (pin "3") (pinfunction "B1_3") (pintype "bidirectional"))
      (node (ref "RT") (pin "2") (pinfunction "2_2") (pintype "passive"))
      (node (ref "SERIAL4") (pin "4") (pinfunction "4_4") (pintype "passive"))
      (node (ref "SERIAL6") (pin "6") (pinfunction "6_6") (pintype "passive"))
      (node (ref "T4") (pin "TP") (pinfunction "TP_TP") (pintype "input"))
      (node (ref "WELL_TEMP") (pin "2") (pinfunction "2_2") (pintype "passive"))
    )
    (net (code "21") (name "Net-(D1-+)") (class "Default")
      (node (ref "D1") (pin "1") (pinfunction "+_1") (pintype "passive"))
      (node (ref "Q4") (pin "3") (pinfunction "C_3") (pintype "passive"))
      (node (ref "RELAY") (pin "P$3") (pinfunction "3_P$3") (pintype "bidirectional"))
    )
    (net (code "22") (name "Net-(D2-+)") (class "Default")
      (node (ref "D2") (pin "1") (pinfunction "+_1") (pintype "passive"))
      (node (ref "Q5") (pin "3") (pinfunction "C_3") (pintype "passive"))
      (node (ref "RELAY") (pin "P$7") (pinfunction "7_P$7") (pintype "bidirectional"))
    )
    (net (code "23") (name "Net-(FANC-S)") (class "Default")
      (node (ref "FAN") (pin "3") (pinfunction "S_3") (pintype "passive"))
      (node (ref "FAN_ON") (pin "2") (pinfunction "2_2") (pintype "passive"))
      (node (ref "Q3") (pin "3") (pinfunction "D_3") (pintype "passive"))
    )
    (net (code "24") (name "Net-(IC1-S)") (class "Default")
      (node (ref "IC1") (pin "P$2") (pinfunction "S_P$2") (pintype "bidirectional"))
      (node (ref "RH") (pin "1") (pinfunction "1_1") (pintype "passive"))
    )
    (net (code "25") (name "Net-(IC2-VBG)") (class "Default")
      (node (ref "C1") (pin "2") (pinfunction "2_2") (pintype "passive"))
      (node (ref "IC2") (pin "P$6") (pinfunction "VBG_P$6") (pintype "bidirectional"))
    )
    (net (code "26") (name "Net-(Q2-D)") (class "Default")
      (node (ref "HEATER_POWER") (pin "2") (pinfunction "2_2") (pintype "bidirectional"))
      (node (ref "Q2") (pin "3") (pinfunction "D_3") (pintype "passive"))
    )
    (net (code "27") (name "Net-(Q2-G)") (class "Default")
      (node (ref "Q2") (pin "1") (pinfunction "G_1") (pintype "passive"))
      (node (ref "R15") (pin "2") (pinfunction "2_2") (pintype "passive"))
      (node (ref "R16") (pin "2") (pinfunction "2_2") (pintype "passive"))
    )
    (net (code "28") (name "Net-(Q3-G)") (class "Default")
      (node (ref "Q3") (pin "1") (pinfunction "G_1") (pintype "passive"))
      (node (ref "R17") (pin "2") (pinfunction "2_2") (pintype "passive"))
      (node (ref "R18") (pin "2") (pinfunction "2_2") (pintype "passive"))
    )
    (net (code "29") (name "Net-(Q4-B)") (class "Default")
      (node (ref "Q4") (pin "1") (pinfunction "B_1") (pintype "passive"))
      (node (ref "R10") (pin "2") (pinfunction "2_2") (pintype "passive"))
    )
    (net (code "30") (name "Net-(Q5-B)") (class "Default")
      (node (ref "Q5") (pin "1") (pinfunction "B_1") (pintype "passive"))
      (node (ref "R11") (pin "1") (pinfunction "1_1") (pintype "passive"))
    )
    (net (code "31") (name "Net-(Q6-B)") (class "Default")
      (node (ref "Q6") (pin "1") (pinfunction "B_1") (pintype "passive"))
      (node (ref "R12") (pin "2") (pinfunction "2_2") (pintype "passive"))
    )
    (net (code "32") (name "Net-(Q6-C)") (class "Default")
      (node (ref "Q1") (pin "G") (pinfunction "G_G") (pintype "passive"))
      (node (ref "Q6") (pin "3") (pinfunction "C_3") (pintype "passive"))
      (node (ref "R13") (pin "1") (pinfunction "1_1") (pintype "passive"))
      (node (ref "R14") (pin "2") (pinfunction "2_2") (pintype "passive"))
    )
    (net (code "33") (name "Net-(RELAY-1)") (class "Default")
      (node (ref "PEL_BLK") (pin "1") (pinfunction "1_1") (pintype "passive"))
      (node (ref "RELAY") (pin "P$1") (pinfunction "1_P$1") (pintype "bidirectional"))
    )
    (net (code "34") (name "Net-(RELAY-5)") (class "Default")
      (node (ref "HEATSINK") (pin "P$1") (pinfunction "P$1_P$1") (pintype "bidirectional"))
      (node (ref "Q1") (pin "D") (pinfunction "D_D") (pintype "passive"))
      (node (ref "RELAY") (pin "P$5") (pinfunction "5_P$5") (pintype "bidirectional"))
    )
    (net (code "35") (name "Net-(RELAY-8)") (class "Default")
      (node (ref "PEL_RED") (pin "1") (pinfunction "1_1") (pintype "passive"))
      (node (ref "RELAY") (pin "P$8") (pinfunction "8_P$8") (pintype "bidirectional"))
    )
    (net (code "36") (name "Net-(RL1-Pad2)") (class "Default")
      (node (ref "RL1") (pin "2") (pinfunction "2_2") (pintype "passive"))
      (node (ref "RL2") (pin "1") (pinfunction "1_1") (pintype "passive"))
    )
    (net (code "37") (name "unconnected-(ATX--12V-Pad14)") (class "Default")
      (node (ref "ATX") (pin "14") (pinfunction "-12V_14") (pintype "bidirectional"))
    )
    (net (code "38") (name "unconnected-(ATX-3V3_1-Pad1)") (class "Default")
      (node (ref "ATX") (pin "1") (pinfunction "3V3_1_1") (pintype "bidirectional"))
    )
    (net (code "39") (name "unconnected-(ATX-3V3_2-Pad2)") (class "Default")
      (node (ref "ATX") (pin "2") (pinfunction "3V3_2_2") (pintype "bidirectional"))
    )
    (net (code "40") (name "unconnected-(ATX-3V3_12-Pad12)") (class "Default")
      (node (ref "ATX") (pin "12") (pinfunction "3V3_12_12") (pintype "bidirectional"))
    )
    (net (code "41") (name "unconnected-(ATX-3V3_13-Pad13)") (class "Default")
      (node (ref "ATX") (pin "13") (pinfunction "3V3_13_13") (pintype "bidirectional"))
    )
    (net (code "42") (name "unconnected-(ATX-5V_4-Pad4)") (class "Default")
      (node (ref "ATX") (pin "4") (pinfunction "5V_4_4") (pintype "bidirectional"))
    )
    (net (code "43") (name "unconnected-(ATX-5V_6-Pad6)") (class "Default")
      (node (ref "ATX") (pin "6") (pinfunction "5V_6_6") (pintype "bidirectional"))
    )
    (net (code "44") (name "unconnected-(ATX-5V_21-Pad21)") (class "Default")
      (node (ref "ATX") (pin "21") (pinfunction "5V_21_21") (pintype "bidirectional"))
    )
    (net (code "45") (name "unconnected-(ATX-5V_22-Pad22)") (class "Default")
      (node (ref "ATX") (pin "22") (pinfunction "5V_22_22") (pintype "bidirectional"))
    )
    (net (code "46") (name "unconnected-(ATX-5V_23-Pad23)") (class "Default")
      (node (ref "ATX") (pin "23") (pinfunction "5V_23_23") (pintype "bidirectional"))
    )
    (net (code "47") (name "unconnected-(ATX-5V_STANDBY-Pad9)") (class "Default")
      (node (ref "ATX") (pin "9") (pinfunction "5V_STANDBY_9") (pintype "bidirectional"))
    )
    (net (code "48") (name "unconnected-(ATX-PWR_GOOD-Pad8)") (class "Default")
      (node (ref "ATX") (pin "8") (pinfunction "PWR_GOOD_8") (pintype "bidirectional"))
    )
    (net (code "49") (name "unconnected-(ATX-PWR_ON-Pad16)") (class "Default")
      (node (ref "ATX") (pin "16") (pinfunction "PWR_ON_16") (pintype "bidirectional"))
    )
    (net (code "50") (name "unconnected-(ATX-RESERVED-Pad20)") (class "Default")
      (node (ref "ATX") (pin "20") (pinfunction "RESERVED_20") (pintype "bidirectional"))
    )
    (net (code "51") (name "unconnected-(ESP-12-CS0-Pad9)") (class "Default")
      (node (ref "ESP-12") (pin "9") (pinfunction "CS0_9") (pintype "bidirectional"))
    )
    (net (code "52") (name "unconnected-(ESP-12-IO9-Pad11)") (class "Default")
      (node (ref "ESP-12") (pin "11") (pinfunction "IO9_11") (pintype "bidirectional"))
    )
    (net (code "53") (name "unconnected-(ESP-12-IO10-Pad12)") (class "Default")
      (node (ref "ESP-12") (pin "12") (pinfunction "IO10_12") (pintype "bidirectional"))
    )
    (net (code "54") (name "unconnected-(ESP-12-MISO-Pad10)") (class "Default")
      (node (ref "ESP-12") (pin "10") (pinfunction "MISO_10") (pintype "bidirectional"))
    )
    (net (code "55") (name "unconnected-(ESP-12-MOSI-Pad13)") (class "Default")
      (node (ref "ESP-12") (pin "13") (pinfunction "MOSI_13") (pintype "bidirectional"))
    )
    (net (code "56") (name "unconnected-(ESP-12-SCLK-Pad14)") (class "Default")
      (node (ref "ESP-12") (pin "14") (pinfunction "SCLK_14") (pintype "bidirectional"))
    )
    (net (code "57") (name "unconnected-(FANA-S-Pad1)") (class "Default")
      (node (ref "FAN") (pin "1") (pinfunction "S_1") (pintype "passive"))
    )
    (net (code "58") (name "unconnected-(IC1-NC-PadP$5)") (class "Default")
      (node (ref "IC1") (pin "P$5") (pinfunction "NC_P$5") (pintype "bidirectional"))
    )
    (net (code "59") (name "unconnected-(IC2-XIN-PadP$10)") (class "Default")
      (node (ref "IC2") (pin "P$10") (pinfunction "XIN_P$10") (pintype "bidirectional"))
    )
    (net (code "60") (name "unconnected-(IC2-XOUT-PadP$11)") (class "Default")
      (node (ref "IC2") (pin "P$11") (pinfunction "XOUT_P$11") (pintype "bidirectional"))
    )
    (net (code "61") (name "unconnected-(SERIAL6-Pad1)") (class "Default")
      (node (ref "SERIAL6") (pin "1") (pinfunction "1_1") (pintype "passive"))
    )
    (net (code "62") (name "unconnected-(SERIAL6-Pad5)") (class "Default")
      (node (ref "SERIAL6") (pin "5") (pinfunction "5_5") (pintype "passive"))
    )
  )
)
